# avionics-controller.net
KiCad netlist of a schematic drawn in EAGLE
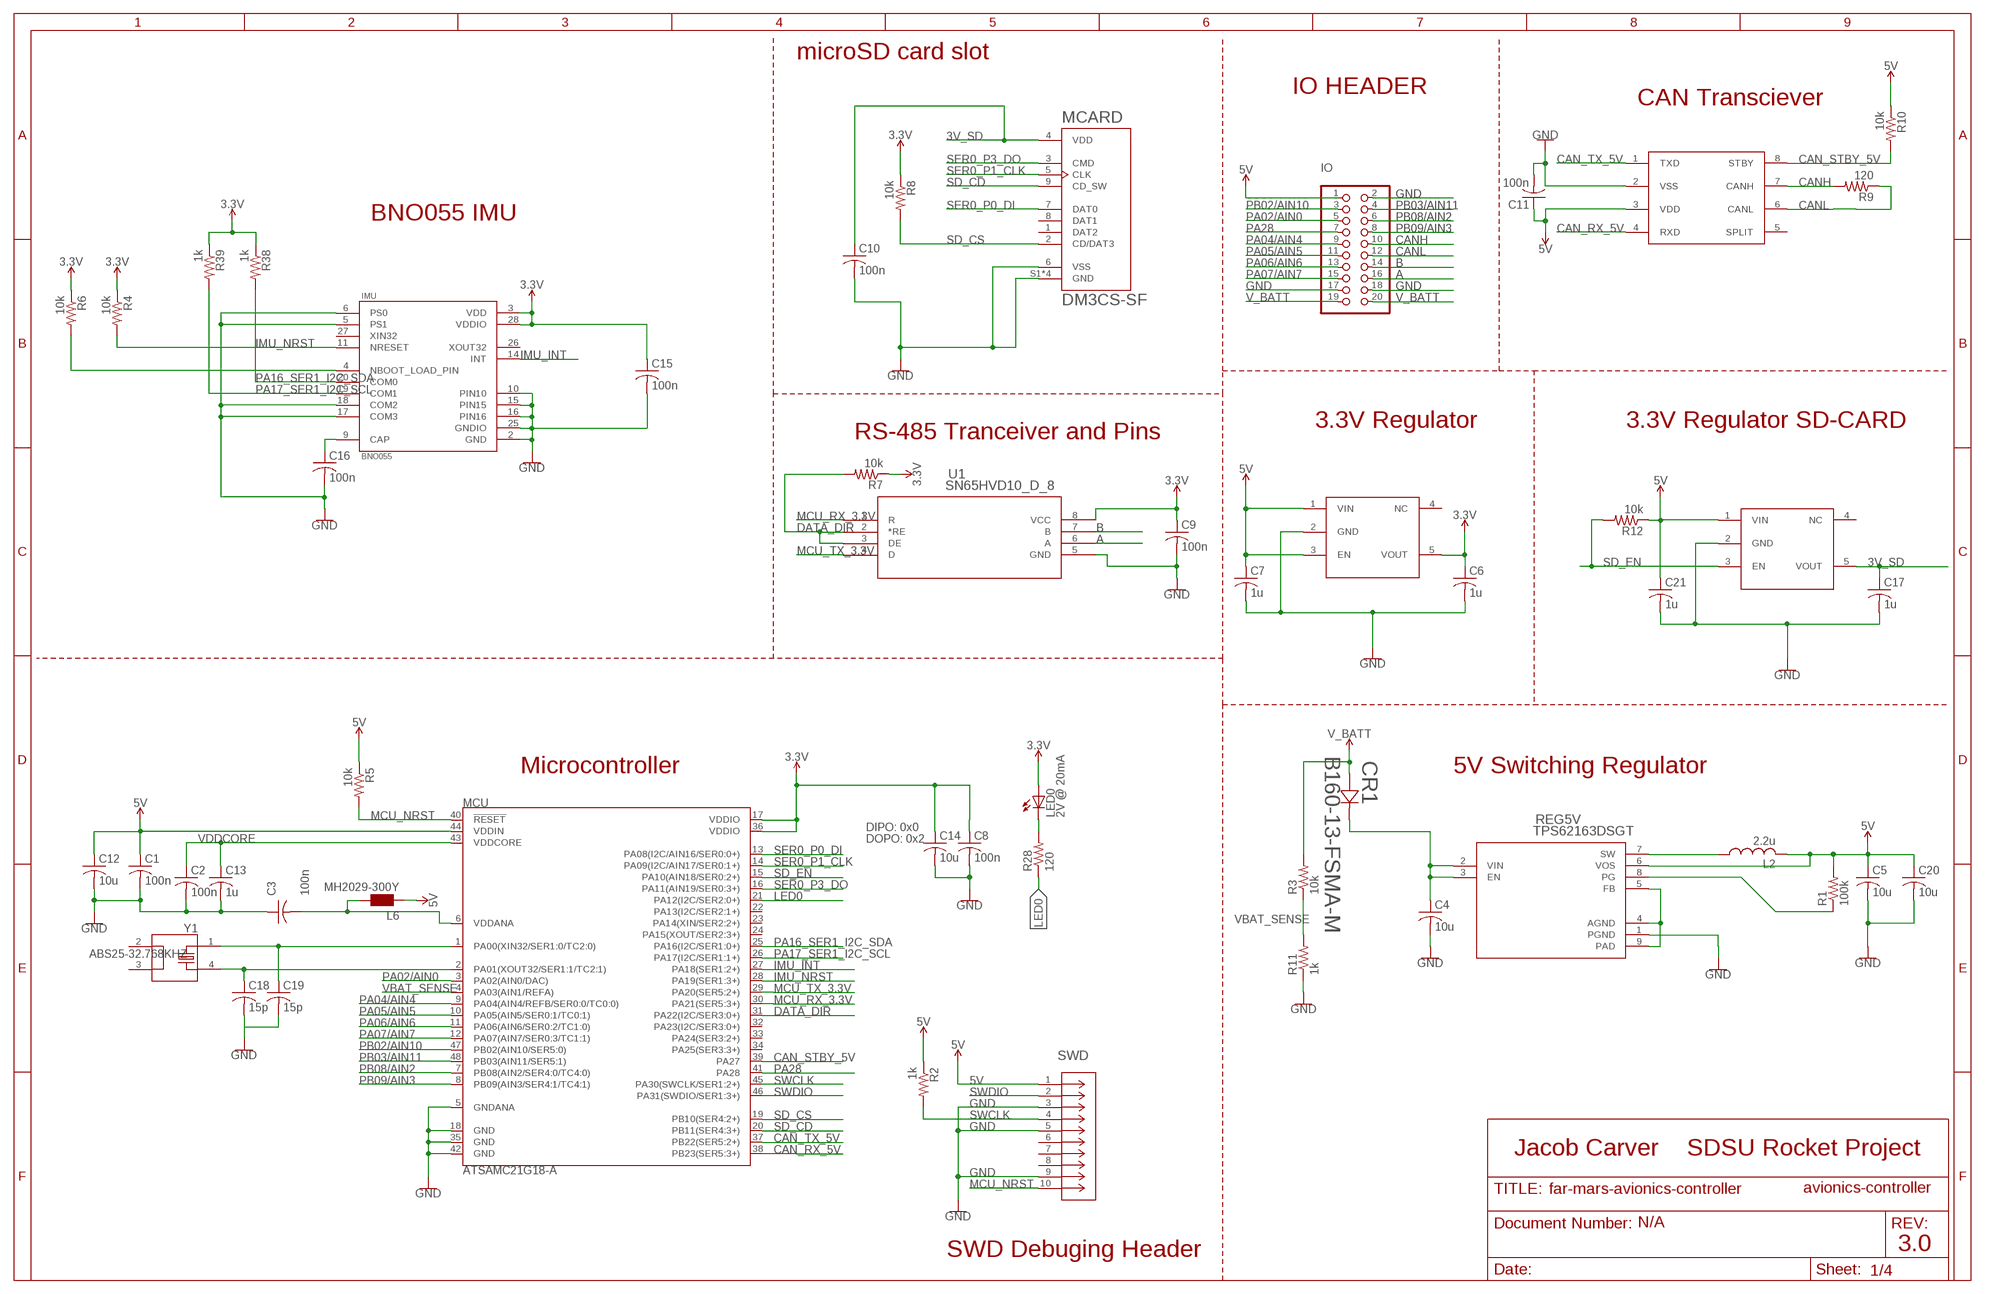
[diagram p0: schematic, sheet 1]

(export (version "E")
  (design (tool "Eeschema 10.0.6"))
  (components
    (comp (ref "3VREG")
      (value "3.3VREGULATOR")
      (footprint "eagle-import:SOT95P280X110-5")
      (libsource (lib "eagle-import") (part "3.3VREGULATOR"))
    )
    (comp (ref "3VREG-SD")
      (value "3.3VREGULATOR")
      (footprint "eagle-import:SOT95P280X110-5")
      (libsource (lib "eagle-import") (part "3.3VREGULATOR"))
    )
    (comp (ref "C1")
      (value "100n")
      (footprint "eagle-import:C0402")
      (libsource (lib "eagle-import") (part "C-USC0402"))
    )
    (comp (ref "C2")
      (value "100n")
      (footprint "eagle-import:C0402")
      (libsource (lib "eagle-import") (part "C-USC0402"))
    )
    (comp (ref "C3")
      (value "100n")
      (footprint "eagle-import:C0402")
      (libsource (lib "eagle-import") (part "C-USC0402"))
    )
    (comp (ref "C4")
      (value "10u")
      (footprint "eagle-import:C0603")
      (libsource (lib "eagle-import") (part "C-USC0603"))
    )
    (comp (ref "C5")
      (value "10u")
      (footprint "eagle-import:C0603")
      (libsource (lib "eagle-import") (part "C-USC0603"))
    )
    (comp (ref "C6")
      (value "1u")
      (footprint "eagle-import:C0402")
      (libsource (lib "eagle-import") (part "C-USC0402"))
    )
    (comp (ref "C7")
      (value "1u")
      (footprint "eagle-import:C0402")
      (libsource (lib "eagle-import") (part "C-USC0402"))
    )
    (comp (ref "C8")
      (value "100n")
      (footprint "eagle-import:C0402")
      (libsource (lib "eagle-import") (part "C-USC0402"))
    )
    (comp (ref "C9")
      (value "100n")
      (footprint "eagle-import:C0402")
      (libsource (lib "eagle-import") (part "C-USC0402"))
    )
    (comp (ref "C10")
      (value "100n")
      (footprint "eagle-import:C0402")
      (libsource (lib "eagle-import") (part "C-USC0402"))
    )
    (comp (ref "C11")
      (value "100n")
      (footprint "eagle-import:C0402")
      (libsource (lib "eagle-import") (part "C-USC0402"))
    )
    (comp (ref "C12")
      (value "10u")
      (footprint "eagle-import:C0603")
      (libsource (lib "eagle-import") (part "C-USC0603"))
    )
    (comp (ref "C13")
      (value "1u")
      (footprint "eagle-import:C0402")
      (libsource (lib "eagle-import") (part "C-USC0402"))
    )
    (comp (ref "C14")
      (value "10u")
      (footprint "eagle-import:C0603")
      (libsource (lib "eagle-import") (part "C-USC0603"))
    )
    (comp (ref "C15")
      (value "100n")
      (footprint "eagle-import:C0402")
      (libsource (lib "eagle-import") (part "C-USC0402"))
    )
    (comp (ref "C16")
      (value "100n")
      (footprint "eagle-import:C0402")
      (libsource (lib "eagle-import") (part "C-USC0402"))
    )
    (comp (ref "C17")
      (value "1u")
      (footprint "eagle-import:C0402")
      (libsource (lib "eagle-import") (part "C-USC0402"))
    )
    (comp (ref "C18")
      (value "15p")
      (footprint "eagle-import:C0402")
      (libsource (lib "eagle-import") (part "C-USC0402"))
    )
    (comp (ref "C19")
      (value "15p")
      (footprint "eagle-import:C0402")
      (libsource (lib "eagle-import") (part "C-USC0402"))
    )
    (comp (ref "C20")
      (value "10u")
      (footprint "eagle-import:C0603")
      (libsource (lib "eagle-import") (part "C-USC0603"))
    )
    (comp (ref "C21")
      (value "1u")
      (footprint "eagle-import:C0402")
      (libsource (lib "eagle-import") (part "C-USC0402"))
    )
    (comp (ref "CAN")
      (value "MCP2561T-E8SOIC")
      (footprint "eagle-import:SOIC127P600X175-8")
      (libsource (lib "eagle-import") (part "MCP2561T-E8SOIC"))
    )
    (comp (ref "CR1")
      (value "B160-13-FSMA-M")
      (footprint "eagle-import:SMA-M")
      (fields (field (name "MANUFACTURER_PART_NUMBER") "B16013F"))
      (libsource (lib "eagle-import") (part "B160-13-FSMA-M"))
    )
    (comp (ref "IMU")
      (value "BNO055")
      (footprint "eagle-import:LGA28R50P4X10_380X520X100")
      (fields (field (name "MF") "Bosch"))
      (libsource (lib "eagle-import") (part "BNO055"))
    )
    (comp (ref "IO")
      (value "PINHD-2X10/90")
      (footprint "eagle-import:2X10_90")
      (libsource (lib "eagle-import") (part "PINHD-2X10/90"))
    )
    (comp (ref "L2")
      (value "2.2u")
      (footprint "eagle-import:L2012C")
      (libsource (lib "eagle-import") (part "L-USL2012C"))
    )
    (comp (ref "L6")
      (value "MH2029-300Y")
      (footprint "eagle-import:0805")
      (fields (field (name "PART_NUMBER") "BLM21PG300SN1D_/_MH2029-300Y"))
      (libsource (lib "eagle-import") (part "0001_BLM21PG300SN1D_/_MH2029-300Y"))
    )
    (comp (ref "LED0")
      (value "2V @ 20mA")
      (footprint "eagle-import:CHIPLED_0603")
      (libsource (lib "eagle-import") (part "LEDCHIPLED_0603"))
    )
    (comp (ref "MCARD")
      (value "DM3CS-SF")
      (footprint "eagle-import:HRS_DM3CS-SF")
      (fields (field (name "DIGI-KEY_PART_NUMBER") "HR1972CT-ND") (field (name "MF") "Hirose"))
      (libsource (lib "eagle-import") (part "DM3CS-SF"))
    )
    (comp (ref "MCU")
      (value "ATSAMC21G18-A")
      (footprint "eagle-import:TQFP-48")
      (libsource (lib "eagle-import") (part "ATSAMD21G-A"))
    )
    (comp (ref "R1")
      (value "100k")
      (footprint "eagle-import:R0402")
      (libsource (lib "eagle-import") (part "R-US_R0402"))
    )
    (comp (ref "R2")
      (value "1k")
      (footprint "eagle-import:R0402")
      (libsource (lib "eagle-import") (part "R-US_R0402"))
    )
    (comp (ref "R3")
      (value "10k")
      (footprint "eagle-import:R0402")
      (libsource (lib "eagle-import") (part "R-US_R0402"))
    )
    (comp (ref "R4")
      (value "10k")
      (footprint "eagle-import:R0402")
      (libsource (lib "eagle-import") (part "R-US_R0402"))
    )
    (comp (ref "R5")
      (value "10k")
      (footprint "eagle-import:R0402")
      (libsource (lib "eagle-import") (part "R-US_R0402"))
    )
    (comp (ref "R6")
      (value "10k")
      (footprint "eagle-import:R0402")
      (libsource (lib "eagle-import") (part "R-US_R0402"))
    )
    (comp (ref "R7")
      (value "10k")
      (footprint "eagle-import:R0402")
      (libsource (lib "eagle-import") (part "R-US_R0402"))
    )
    (comp (ref "R8")
      (value "10k")
      (footprint "eagle-import:R0402")
      (libsource (lib "eagle-import") (part "R-US_R0402"))
    )
    (comp (ref "R9")
      (value "120")
      (footprint "eagle-import:R0402")
      (libsource (lib "eagle-import") (part "R-US_R0402"))
    )
    (comp (ref "R10")
      (value "10k")
      (footprint "eagle-import:R0402")
      (libsource (lib "eagle-import") (part "R-US_R0402"))
    )
    (comp (ref "R11")
      (value "1k")
      (footprint "eagle-import:R0402")
      (libsource (lib "eagle-import") (part "R-US_R0402"))
    )
    (comp (ref "R12")
      (value "10k")
      (footprint "eagle-import:R0402")
      (libsource (lib "eagle-import") (part "R-US_R0402"))
    )
    (comp (ref "R28")
      (value "120")
      (footprint "eagle-import:R0402")
      (libsource (lib "eagle-import") (part "R-US_R0402"))
    )
    (comp (ref "R38")
      (value "1k")
      (footprint "eagle-import:R0402")
      (libsource (lib "eagle-import") (part "R-US_R0402"))
    )
    (comp (ref "R39")
      (value "1k")
      (footprint "eagle-import:R0402")
      (libsource (lib "eagle-import") (part "R-US_R0402"))
    )
    (comp (ref "REG5V")
      (value "TPS62163DSGT")
      (footprint "eagle-import:DSG8_1P6X0P9")
      (libsource (lib "eagle-import") (part "TPS62163DSGT"))
    )
    (comp (ref "SWD")
      (value "DEBUG-HEADER")
      (footprint "eagle-import:CONN_MINITEK_2X5_HDR")
      (fields (field (name "MANUFACTURER_PART_NUMBER") "2002111100010T4LF"))
      (libsource (lib "eagle-import") (part "DEBUG-HEADER"))
    )
    (comp (ref "U1")
      (value "SN65HVD10_D_8")
      (footprint "eagle-import:D8")
      (fields
        (field (name "GENERIC_PART_NUMBER") "SN65HVD10")
        (field (name "MANUFACTURER") "Texas Instruments")
        (field (name "MANUFACTURER_PART_NUMBER") "sn65hvd10_d_8")
      )
      (libsource (lib "eagle-import") (part "SN65HVD10_D_8"))
    )
    (comp (ref "Y1")
      (value "ABS25-32.768KHZ")
      (footprint "eagle-import:ABS25-32.768KHZ-6-T")
      (fields
        (field (name "DIGI-KEY_PART_NUMBER") "XC1307CT-ND")
        (field (name "MF") "ECS Inc.")
        (field (name "MP") "ECS-.327-6-17X-TR")
      )
      (libsource (lib "eagle-import") (part "ABS25-32.768KHZ"))
    )
  )
  (nets
    (net (code "1") (name "3.3V") (class "Default")
      (node (ref "3VREG") (pin "5") (pinfunction "VOUT_5") (pintype "bidirectional"))
      (node (ref "C14") (pin "1") (pinfunction "1_1") (pintype "passive"))
      (node (ref "C15") (pin "1") (pinfunction "1_1") (pintype "passive"))
      (node (ref "C6") (pin "1") (pinfunction "1_1") (pintype "passive"))
      (node (ref "C8") (pin "1") (pinfunction "1_1") (pintype "passive"))
      (node (ref "C9") (pin "1") (pinfunction "1_1") (pintype "passive"))
      (node (ref "IMU") (pin "28") (pinfunction "VDDIO_28") (pintype "power_in"))
      (node (ref "IMU") (pin "3") (pinfunction "VDD_3") (pintype "power_in"))
      (node (ref "LED0") (pin "A") (pinfunction "A_A") (pintype "passive"))
      (node (ref "MCU") (pin "17") (pinfunction "VDDIO_17") (pintype "bidirectional"))
      (node (ref "MCU") (pin "36") (pinfunction "VDDIO_36") (pintype "bidirectional"))
      (node (ref "R38") (pin "1") (pinfunction "1_1") (pintype "passive"))
      (node (ref "R39") (pin "1") (pinfunction "1_1") (pintype "passive"))
      (node (ref "R4") (pin "1") (pinfunction "1_1") (pintype "passive"))
      (node (ref "R6") (pin "1") (pinfunction "1_1") (pintype "passive"))
      (node (ref "R7") (pin "1") (pinfunction "1_1") (pintype "passive"))
      (node (ref "R8") (pin "1") (pinfunction "1_1") (pintype "passive"))
      (node (ref "U1") (pin "8") (pinfunction "VCC_8") (pintype "power_in"))
    )
    (net (code "2") (name "3V_SD") (class "Default")
      (node (ref "3VREG-SD") (pin "5") (pinfunction "VOUT_5") (pintype "bidirectional"))
      (node (ref "C10") (pin "1") (pinfunction "1_1") (pintype "passive"))
      (node (ref "C17") (pin "1") (pinfunction "1_1") (pintype "passive"))
      (node (ref "MCARD") (pin "4") (pinfunction "VDD_4") (pintype "passive"))
    )
    (net (code "3") (name "5V") (class "Default")
      (node (ref "3VREG") (pin "1") (pinfunction "VIN_1") (pintype "bidirectional"))
      (node (ref "3VREG") (pin "3") (pinfunction "EN_3") (pintype "bidirectional"))
      (node (ref "3VREG-SD") (pin "1") (pinfunction "VIN_1") (pintype "bidirectional"))
      (node (ref "C1") (pin "1") (pinfunction "1_1") (pintype "passive"))
      (node (ref "C11") (pin "1") (pinfunction "1_1") (pintype "passive"))
      (node (ref "C12") (pin "1") (pinfunction "1_1") (pintype "passive"))
      (node (ref "C20") (pin "1") (pinfunction "1_1") (pintype "passive"))
      (node (ref "C21") (pin "1") (pinfunction "1_1") (pintype "passive"))
      (node (ref "C5") (pin "1") (pinfunction "1_1") (pintype "passive"))
      (node (ref "C7") (pin "1") (pinfunction "1_1") (pintype "passive"))
      (node (ref "CAN") (pin "3") (pinfunction "VDD_3") (pintype "power_in"))
      (node (ref "IO") (pin "1") (pinfunction "1_1") (pintype "passive"))
      (node (ref "L2") (pin "2") (pinfunction "2_2") (pintype "passive"))
      (node (ref "L6") (pin "1") (pinfunction "1_1") (pintype "passive"))
      (node (ref "MCU") (pin "44") (pinfunction "VDDIN_44") (pintype "bidirectional"))
      (node (ref "R1") (pin "2") (pinfunction "2_2") (pintype "passive"))
      (node (ref "R10") (pin "1") (pinfunction "1_1") (pintype "passive"))
      (node (ref "R12") (pin "1") (pinfunction "1_1") (pintype "passive"))
      (node (ref "R2") (pin "1") (pinfunction "1_1") (pintype "passive"))
      (node (ref "R5") (pin "1") (pinfunction "1_1") (pintype "passive"))
      (node (ref "REG5V") (pin "6") (pinfunction "VOS_6") (pintype "input"))
      (node (ref "SWD") (pin "1") (pinfunction "1_1") (pintype "passive"))
    )
    (net (code "4") (name "A") (class "Default")
      (node (ref "IO") (pin "16") (pinfunction "16_16") (pintype "passive"))
      (node (ref "U1") (pin "6") (pinfunction "A_6") (pintype "input"))
    )
    (net (code "5") (name "B") (class "Default")
      (node (ref "IO") (pin "14") (pinfunction "14_14") (pintype "passive"))
      (node (ref "U1") (pin "7") (pinfunction "B_7") (pintype "input"))
    )
    (net (code "6") (name "CANH") (class "Default")
      (node (ref "CAN") (pin "7") (pinfunction "CANH_7") (pintype "bidirectional"))
      (node (ref "IO") (pin "10") (pinfunction "10_10") (pintype "passive"))
      (node (ref "R9") (pin "2") (pinfunction "2_2") (pintype "passive"))
    )
    (net (code "7") (name "CANL") (class "Default")
      (node (ref "CAN") (pin "6") (pinfunction "CANL_6") (pintype "bidirectional"))
      (node (ref "IO") (pin "12") (pinfunction "12_12") (pintype "passive"))
      (node (ref "R9") (pin "1") (pinfunction "1_1") (pintype "passive"))
    )
    (net (code "8") (name "CAN_RX_5V") (class "Default")
      (node (ref "CAN") (pin "4") (pinfunction "RXD_4") (pintype "bidirectional"))
      (node (ref "MCU") (pin "38") (pinfunction "PB23(SER5:3+)_38") (pintype "bidirectional"))
    )
    (net (code "9") (name "CAN_STBY_5V") (class "Default")
      (node (ref "CAN") (pin "8") (pinfunction "STBY_8") (pintype "bidirectional"))
      (node (ref "MCU") (pin "39") (pinfunction "PA27_39") (pintype "bidirectional"))
      (node (ref "R10") (pin "2") (pinfunction "2_2") (pintype "passive"))
    )
    (net (code "10") (name "CAN_TX_5V") (class "Default")
      (node (ref "CAN") (pin "1") (pinfunction "TXD_1") (pintype "bidirectional"))
      (node (ref "MCU") (pin "37") (pinfunction "PB22(SER5:2+)_37") (pintype "bidirectional"))
    )
    (net (code "11") (name "DATA_DIR") (class "Default")
      (node (ref "MCU") (pin "31") (pinfunction "PA22(I2C/SER3:0+)_31") (pintype "bidirectional"))
      (node (ref "R7") (pin "2") (pinfunction "2_2") (pintype "passive"))
      (node (ref "U1") (pin "2") (pinfunction "*RE_2") (pintype "input"))
      (node (ref "U1") (pin "3") (pinfunction "DE_3") (pintype "input"))
    )
    (net (code "12") (name "GND") (class "Default")
      (node (ref "3VREG") (pin "2") (pinfunction "GND_2") (pintype "bidirectional"))
      (node (ref "3VREG-SD") (pin "2") (pinfunction "GND_2") (pintype "bidirectional"))
      (node (ref "C1") (pin "2") (pinfunction "2_2") (pintype "passive"))
      (node (ref "C10") (pin "2") (pinfunction "2_2") (pintype "passive"))
      (node (ref "C11") (pin "2") (pinfunction "2_2") (pintype "passive"))
      (node (ref "C12") (pin "2") (pinfunction "2_2") (pintype "passive"))
      (node (ref "C13") (pin "2") (pinfunction "2_2") (pintype "passive"))
      (node (ref "C14") (pin "2") (pinfunction "2_2") (pintype "passive"))
      (node (ref "C15") (pin "2") (pinfunction "2_2") (pintype "passive"))
      (node (ref "C16") (pin "2") (pinfunction "2_2") (pintype "passive"))
      (node (ref "C17") (pin "2") (pinfunction "2_2") (pintype "passive"))
      (node (ref "C18") (pin "2") (pinfunction "2_2") (pintype "passive"))
      (node (ref "C19") (pin "2") (pinfunction "2_2") (pintype "passive"))
      (node (ref "C2") (pin "2") (pinfunction "2_2") (pintype "passive"))
      (node (ref "C20") (pin "2") (pinfunction "2_2") (pintype "passive"))
      (node (ref "C21") (pin "2") (pinfunction "2_2") (pintype "passive"))
      (node (ref "C3") (pin "1") (pinfunction "1_1") (pintype "passive"))
      (node (ref "C4") (pin "2") (pinfunction "2_2") (pintype "passive"))
      (node (ref "C5") (pin "2") (pinfunction "2_2") (pintype "passive"))
      (node (ref "C6") (pin "2") (pinfunction "2_2") (pintype "passive"))
      (node (ref "C7") (pin "2") (pinfunction "2_2") (pintype "passive"))
      (node (ref "C8") (pin "2") (pinfunction "2_2") (pintype "passive"))
      (node (ref "C9") (pin "2") (pinfunction "2_2") (pintype "passive"))
      (node (ref "CAN") (pin "2") (pinfunction "VSS_2") (pintype "power_in"))
      (node (ref "IMU") (pin "10") (pinfunction "PIN10_10") (pintype "power_in"))
      (node (ref "IMU") (pin "15") (pinfunction "PIN15_15") (pintype "power_in"))
      (node (ref "IMU") (pin "16") (pinfunction "PIN16_16") (pintype "power_in"))
      (node (ref "IMU") (pin "17") (pinfunction "COM3_17") (pintype "bidirectional"))
      (node (ref "IMU") (pin "18") (pinfunction "COM2_18") (pintype "bidirectional"))
      (node (ref "IMU") (pin "2") (pinfunction "GND_2") (pintype "power_in"))
      (node (ref "IMU") (pin "25") (pinfunction "GNDIO_25") (pintype "power_in"))
      (node (ref "IMU") (pin "5") (pinfunction "PS1_5") (pintype "input"))
      (node (ref "IMU") (pin "6") (pinfunction "PS0_6") (pintype "input"))
      (node (ref "IO") (pin "17") (pinfunction "17_17") (pintype "passive"))
      (node (ref "IO") (pin "18") (pinfunction "18_18") (pintype "passive"))
      (node (ref "IO") (pin "2") (pinfunction "2_2") (pintype "passive"))
      (node (ref "MCARD") (pin "6") (pinfunction "VSS_6") (pintype "passive"))
      (node (ref "MCARD") (pin "S1") (pinfunction "GND_S1") (pintype "passive"))
      (node (ref "MCARD") (pin "S2") (pinfunction "GND_S2") (pintype "passive"))
      (node (ref "MCARD") (pin "S3") (pinfunction "GND_S3") (pintype "passive"))
      (node (ref "MCARD") (pin "S5") (pinfunction "GND_S5") (pintype "passive"))
      (node (ref "MCU") (pin "18") (pinfunction "GND_18") (pintype "bidirectional"))
      (node (ref "MCU") (pin "35") (pinfunction "GND_35") (pintype "bidirectional"))
      (node (ref "MCU") (pin "42") (pinfunction "GND_42") (pintype "bidirectional"))
      (node (ref "MCU") (pin "5") (pinfunction "GNDANA_5") (pintype "bidirectional"))
      (node (ref "R11") (pin "1") (pinfunction "1_1") (pintype "passive"))
      (node (ref "REG5V") (pin "1") (pinfunction "PGND_1") (pintype "power_in"))
      (node (ref "SWD") (pin "3") (pinfunction "3_3") (pintype "passive"))
      (node (ref "SWD") (pin "5") (pinfunction "5_5") (pintype "passive"))
      (node (ref "SWD") (pin "9") (pinfunction "9_9") (pintype "passive"))
      (node (ref "U1") (pin "5") (pinfunction "GND_5") (pintype "power_in"))
    )
    (net (code "13") (name "IMU_INT") (class "Default")
      (node (ref "IMU") (pin "14") (pinfunction "INT_14") (pintype "output"))
      (node (ref "MCU") (pin "27") (pinfunction "PA18(SER1:2+)_27") (pintype "bidirectional"))
    )
    (net (code "14") (name "IMU_NRST") (class "Default")
      (node (ref "IMU") (pin "11") (pinfunction "NRESET_11") (pintype "input"))
      (node (ref "MCU") (pin "28") (pinfunction "PA19(SER1:3+)_28") (pintype "bidirectional"))
      (node (ref "R4") (pin "2") (pinfunction "2_2") (pintype "passive"))
    )
    (net (code "15") (name "LED0") (class "Default")
      (node (ref "MCU") (pin "21") (pinfunction "PA12(I2C/SER2:0+)_21") (pintype "bidirectional"))
      (node (ref "R28") (pin "1") (pinfunction "1_1") (pintype "passive"))
    )
    (net (code "16") (name "MCU_NRST") (class "Default")
      (node (ref "MCU") (pin "40") (pinfunction "~{RESET}_40") (pintype "bidirectional"))
      (node (ref "R5") (pin "2") (pinfunction "2_2") (pintype "passive"))
      (node (ref "SWD") (pin "10") (pinfunction "10_10") (pintype "passive"))
    )
    (net (code "17") (name "MCU_RX_3.3V") (class "Default")
      (node (ref "MCU") (pin "30") (pinfunction "PA21(SER5:3+)_30") (pintype "bidirectional"))
      (node (ref "U1") (pin "1") (pinfunction "R_1") (pintype "input"))
    )
    (net (code "18") (name "MCU_TX_3.3V") (class "Default")
      (node (ref "MCU") (pin "29") (pinfunction "PA20(SER5:2+)_29") (pintype "bidirectional"))
      (node (ref "U1") (pin "4") (pinfunction "D_4") (pintype "input"))
    )
    (net (code "19") (name "Net-(CR1-12)") (class "Default")
      (node (ref "C4") (pin "1") (pinfunction "1_1") (pintype "passive"))
      (node (ref "CR1") (pin "1") (pinfunction "12_1") (pintype "passive"))
      (node (ref "REG5V") (pin "2") (pinfunction "VIN_2") (pintype "input"))
      (node (ref "REG5V") (pin "3") (pinfunction "EN_3") (pintype "input"))
    )
    (net (code "20") (name "Net-(IMU-CAP)") (class "Default")
      (node (ref "C16") (pin "1") (pinfunction "1_1") (pintype "passive"))
      (node (ref "IMU") (pin "9") (pinfunction "CAP_9") (pintype "passive"))
    )
    (net (code "21") (name "Net-(IMU-NBOOT_LOAD_PIN)") (class "Default")
      (node (ref "IMU") (pin "4") (pinfunction "NBOOT_LOAD_PIN_4") (pintype "bidirectional"))
      (node (ref "R6") (pin "2") (pinfunction "2_2") (pintype "passive"))
    )
    (net (code "22") (name "Net-(LED0-PadC)") (class "Default")
      (node (ref "LED0") (pin "C") (pinfunction "C_C") (pintype "passive"))
      (node (ref "R28") (pin "2") (pinfunction "2_2") (pintype "passive"))
    )
    (net (code "23") (name "Net-(MCU-PA00(XIN32{slash}SER1:0{slash}TC2:0))") (class "Default")
      (node (ref "C19") (pin "1") (pinfunction "1_1") (pintype "passive"))
      (node (ref "MCU") (pin "1") (pinfunction "PA00(XIN32/SER1:0/TC2:0)_1") (pintype "bidirectional"))
      (node (ref "Y1") (pin "1") (pinfunction "1_1") (pintype "passive"))
    )
    (net (code "24") (name "Net-(MCU-PA01(XOUT32{slash}SER1:1{slash}TC2:1))") (class "Default")
      (node (ref "C18") (pin "1") (pinfunction "1_1") (pintype "passive"))
      (node (ref "MCU") (pin "2") (pinfunction "PA01(XOUT32/SER1:1/TC2:1)_2") (pintype "bidirectional"))
      (node (ref "Y1") (pin "4") (pinfunction "4_4") (pintype "passive"))
    )
    (net (code "25") (name "Net-(MCU-VDDANA)") (class "Default")
      (node (ref "C3") (pin "2") (pinfunction "2_2") (pintype "passive"))
      (node (ref "L6") (pin "2") (pinfunction "2_2") (pintype "passive"))
      (node (ref "MCU") (pin "6") (pinfunction "VDDANA_6") (pintype "bidirectional"))
    )
    (net (code "26") (name "Net-(REG5V-AGND)") (class "Default")
      (node (ref "REG5V") (pin "4") (pinfunction "AGND_4") (pintype "power_in"))
      (node (ref "REG5V") (pin "5") (pinfunction "FB_5") (pintype "input"))
      (node (ref "REG5V") (pin "9") (pinfunction "PAD_9") (pintype "bidirectional"))
    )
    (net (code "27") (name "Net-(REG5V-PG)") (class "Default")
      (node (ref "R1") (pin "1") (pinfunction "1_1") (pintype "passive"))
      (node (ref "REG5V") (pin "8") (pinfunction "PG_8") (pintype "bidirectional"))
    )
    (net (code "28") (name "Net-(REG5V-SW)") (class "Default")
      (node (ref "L2") (pin "1") (pinfunction "1_1") (pintype "passive"))
      (node (ref "REG5V") (pin "7") (pinfunction "SW_7") (pintype "output"))
    )
    (net (code "29") (name "PA02{slash}AIN0") (class "Default")
      (node (ref "IO") (pin "5") (pinfunction "5_5") (pintype "passive"))
      (node (ref "MCU") (pin "3") (pinfunction "PA02(AIN0/DAC)_3") (pintype "bidirectional"))
    )
    (net (code "30") (name "PA04{slash}AIN4") (class "Default")
      (node (ref "IO") (pin "9") (pinfunction "9_9") (pintype "passive"))
      (node (ref "MCU") (pin "9") (pinfunction "PA04(AIN4/REFB/SER0:0/TC0:0)_9") (pintype "bidirectional"))
    )
    (net (code "31") (name "PA05{slash}AIN5") (class "Default")
      (node (ref "IO") (pin "11") (pinfunction "11_11") (pintype "passive"))
      (node (ref "MCU") (pin "10") (pinfunction "PA05(AIN5/SER0:1/TC0:1)_10") (pintype "bidirectional"))
    )
    (net (code "32") (name "PA06{slash}AIN6") (class "Default")
      (node (ref "IO") (pin "13") (pinfunction "13_13") (pintype "passive"))
      (node (ref "MCU") (pin "11") (pinfunction "PA06(AIN6/SER0:2/TC1:0)_11") (pintype "bidirectional"))
    )
    (net (code "33") (name "PA07{slash}AIN7") (class "Default")
      (node (ref "IO") (pin "15") (pinfunction "15_15") (pintype "passive"))
      (node (ref "MCU") (pin "12") (pinfunction "PA07(AIN7/SER0:3/TC1:1)_12") (pintype "bidirectional"))
    )
    (net (code "34") (name "PA16_SER1_I2C_SDA") (class "Default")
      (node (ref "IMU") (pin "20") (pinfunction "COM0_20") (pintype "bidirectional"))
      (node (ref "MCU") (pin "25") (pinfunction "PA16(I2C/SER1:0+)_25") (pintype "bidirectional"))
      (node (ref "R38") (pin "2") (pinfunction "2_2") (pintype "passive"))
    )
    (net (code "35") (name "PA17_SER1_I2C_SCL") (class "Default")
      (node (ref "IMU") (pin "19") (pinfunction "COM1_19") (pintype "bidirectional"))
      (node (ref "MCU") (pin "26") (pinfunction "PA17(I2C/SER1:1+)_26") (pintype "bidirectional"))
      (node (ref "R39") (pin "2") (pinfunction "2_2") (pintype "passive"))
    )
    (net (code "36") (name "PA28") (class "Default")
      (node (ref "IO") (pin "7") (pinfunction "7_7") (pintype "passive"))
      (node (ref "MCU") (pin "41") (pinfunction "PA28_41") (pintype "bidirectional"))
    )
    (net (code "37") (name "PB02{slash}AIN10") (class "Default")
      (node (ref "IO") (pin "3") (pinfunction "3_3") (pintype "passive"))
      (node (ref "MCU") (pin "47") (pinfunction "PB02(AIN10/SER5:0)_47") (pintype "bidirectional"))
    )
    (net (code "38") (name "PB03{slash}AIN11") (class "Default")
      (node (ref "IO") (pin "4") (pinfunction "4_4") (pintype "passive"))
      (node (ref "MCU") (pin "48") (pinfunction "PB03(AIN11/SER5:1)_48") (pintype "bidirectional"))
    )
    (net (code "39") (name "PB08{slash}AIN2") (class "Default")
      (node (ref "IO") (pin "6") (pinfunction "6_6") (pintype "passive"))
      (node (ref "MCU") (pin "7") (pinfunction "PB08(AIN2/SER4:0/TC4:0)_7") (pintype "bidirectional"))
    )
    (net (code "40") (name "PB09{slash}AIN3") (class "Default")
      (node (ref "IO") (pin "8") (pinfunction "8_8") (pintype "passive"))
      (node (ref "MCU") (pin "8") (pinfunction "PB09(AIN3/SER4:1/TC4:1)_8") (pintype "bidirectional"))
    )
    (net (code "41") (name "SD_CD") (class "Default")
      (node (ref "MCARD") (pin "9") (pinfunction "CD_SW_9") (pintype "passive"))
      (node (ref "MCU") (pin "20") (pinfunction "PB11(SER4:3+)_20") (pintype "bidirectional"))
    )
    (net (code "42") (name "SD_CS") (class "Default")
      (node (ref "MCARD") (pin "2") (pinfunction "CD/DAT3_2") (pintype "passive"))
      (node (ref "MCU") (pin "19") (pinfunction "PB10(SER4:2+)_19") (pintype "bidirectional"))
      (node (ref "R8") (pin "2") (pinfunction "2_2") (pintype "passive"))
    )
    (net (code "43") (name "SD_EN") (class "Default")
      (node (ref "3VREG-SD") (pin "3") (pinfunction "EN_3") (pintype "bidirectional"))
      (node (ref "MCU") (pin "15") (pinfunction "PA10(AIN18/SER0:2+)_15") (pintype "bidirectional"))
      (node (ref "R12") (pin "2") (pinfunction "2_2") (pintype "passive"))
    )
    (net (code "44") (name "SER0_P0_DI") (class "Default")
      (node (ref "MCARD") (pin "7") (pinfunction "DAT0_7") (pintype "passive"))
      (node (ref "MCU") (pin "13") (pinfunction "PA08(I2C/AIN16/SER0:0+)_13") (pintype "bidirectional"))
    )
    (net (code "45") (name "SER0_P1_CLK") (class "Default")
      (node (ref "MCARD") (pin "5") (pinfunction "CLK_5") (pintype "passive"))
      (node (ref "MCU") (pin "14") (pinfunction "PA09(I2C/AIN17/SER0:1+)_14") (pintype "bidirectional"))
    )
    (net (code "46") (name "SER0_P3_DO") (class "Default")
      (node (ref "MCARD") (pin "3") (pinfunction "CMD_3") (pintype "passive"))
      (node (ref "MCU") (pin "16") (pinfunction "PA11(AIN19/SER0:3+)_16") (pintype "bidirectional"))
    )
    (net (code "47") (name "SWCLK") (class "Default")
      (node (ref "MCU") (pin "45") (pinfunction "PA30(SWCLK/SER1:2+)_45") (pintype "bidirectional"))
      (node (ref "R2") (pin "2") (pinfunction "2_2") (pintype "passive"))
      (node (ref "SWD") (pin "4") (pinfunction "4_4") (pintype "passive"))
    )
    (net (code "48") (name "SWDIO") (class "Default")
      (node (ref "MCU") (pin "46") (pinfunction "PA31(SWDIO/SER1:3+)_46") (pintype "bidirectional"))
      (node (ref "SWD") (pin "2") (pinfunction "2_2") (pintype "passive"))
    )
    (net (code "49") (name "VBAT_SENSE") (class "Default")
      (node (ref "MCU") (pin "4") (pinfunction "PA03(AIN1/REFA)_4") (pintype "bidirectional"))
      (node (ref "R11") (pin "2") (pinfunction "2_2") (pintype "passive"))
      (node (ref "R3") (pin "1") (pinfunction "1_1") (pintype "passive"))
    )
    (net (code "50") (name "VDDCORE") (class "Default")
      (node (ref "C13") (pin "1") (pinfunction "1_1") (pintype "passive"))
      (node (ref "C2") (pin "1") (pinfunction "1_1") (pintype "passive"))
      (node (ref "MCU") (pin "43") (pinfunction "VDDCORE_43") (pintype "bidirectional"))
    )
    (net (code "51") (name "V_BATT") (class "Default")
      (node (ref "CR1") (pin "2") (pinfunction "21_2") (pintype "passive"))
      (node (ref "IO") (pin "19") (pinfunction "19_19") (pintype "passive"))
      (node (ref "IO") (pin "20") (pinfunction "20_20") (pintype "passive"))
      (node (ref "R3") (pin "2") (pinfunction "2_2") (pintype "passive"))
    )
    (net (code "52") (name "unconnected-(3VREG-NC-Pad4)") (class "Default")
      (node (ref "3VREG") (pin "4") (pinfunction "NC_4") (pintype "bidirectional"))
    )
    (net (code "53") (name "unconnected-(3VREG-SD-NC-Pad4)") (class "Default")
      (node (ref "3VREG-SD") (pin "4") (pinfunction "NC_4") (pintype "bidirectional"))
    )
    (net (code "54") (name "unconnected-(CAN-SPLIT-Pad5)") (class "Default")
      (node (ref "CAN") (pin "5") (pinfunction "SPLIT_5") (pintype "bidirectional"))
    )
    (net (code "55") (name "unconnected-(IMU-XIN32-Pad27)") (class "Default")
      (node (ref "IMU") (pin "27") (pinfunction "XIN32_27") (pintype "input"))
    )
    (net (code "56") (name "unconnected-(IMU-XOUT32-Pad26)") (class "Default")
      (node (ref "IMU") (pin "26") (pinfunction "XOUT32_26") (pintype "output"))
    )
    (net (code "57") (name "unconnected-(MCARD-DAT1-Pad8)") (class "Default")
      (node (ref "MCARD") (pin "8") (pinfunction "DAT1_8") (pintype "passive"))
    )
    (net (code "58") (name "unconnected-(MCARD-DAT2-Pad1)") (class "Default")
      (node (ref "MCARD") (pin "1") (pinfunction "DAT2_1") (pintype "passive"))
    )
    (net (code "59") (name "unconnected-(MCU-PA13(I2C{slash}SER2:1+)-Pad22)") (class "Default")
      (node (ref "MCU") (pin "22") (pinfunction "PA13(I2C/SER2:1+)_22") (pintype "bidirectional"))
    )
    (net (code "60") (name "unconnected-(MCU-PA14(XIN{slash}SER2:2+)-Pad23)") (class "Default")
      (node (ref "MCU") (pin "23") (pinfunction "PA14(XIN/SER2:2+)_23") (pintype "bidirectional"))
    )
    (net (code "61") (name "unconnected-(MCU-PA15(XOUT{slash}SER2:3+)-Pad24)") (class "Default")
      (node (ref "MCU") (pin "24") (pinfunction "PA15(XOUT/SER2:3+)_24") (pintype "bidirectional"))
    )
    (net (code "62") (name "unconnected-(MCU-PA23(I2C{slash}SER3:0+)-Pad32)") (class "Default")
      (node (ref "MCU") (pin "32") (pinfunction "PA23(I2C/SER3:0+)_32") (pintype "bidirectional"))
    )
    (net (code "63") (name "unconnected-(MCU-PA24(SER3:2+)-Pad33)") (class "Default")
      (node (ref "MCU") (pin "33") (pinfunction "PA24(SER3:2+)_33") (pintype "bidirectional"))
    )
    (net (code "64") (name "unconnected-(MCU-PA25(SER3:3+)-Pad34)") (class "Default")
      (node (ref "MCU") (pin "34") (pinfunction "PA25(SER3:3+)_34") (pintype "bidirectional"))
    )
    (net (code "65") (name "unconnected-(SWD-Pad6)") (class "Default")
      (node (ref "SWD") (pin "6") (pinfunction "6_6") (pintype "passive"))
    )
    (net (code "66") (name "unconnected-(SWD-Pad7)") (class "Default")
      (node (ref "SWD") (pin "7") (pinfunction "7_7") (pintype "passive"))
    )
    (net (code "67") (name "unconnected-(SWD-Pad8)") (class "Default")
      (node (ref "SWD") (pin "8") (pinfunction "8_8") (pintype "passive"))
    )
    (net (code "68") (name "unconnected-(Y1-Pad2)") (class "Default")
      (node (ref "Y1") (pin "2") (pinfunction "2_2") (pintype "passive"))
    )
    (net (code "69") (name "unconnected-(Y1-Pad3)") (class "Default")
      (node (ref "Y1") (pin "3") (pinfunction "3_3") (pintype "passive"))
    )
  )
)
